# Wash_Hand_v1_3.net
KiCad netlist of a schematic drawn in EAGLE
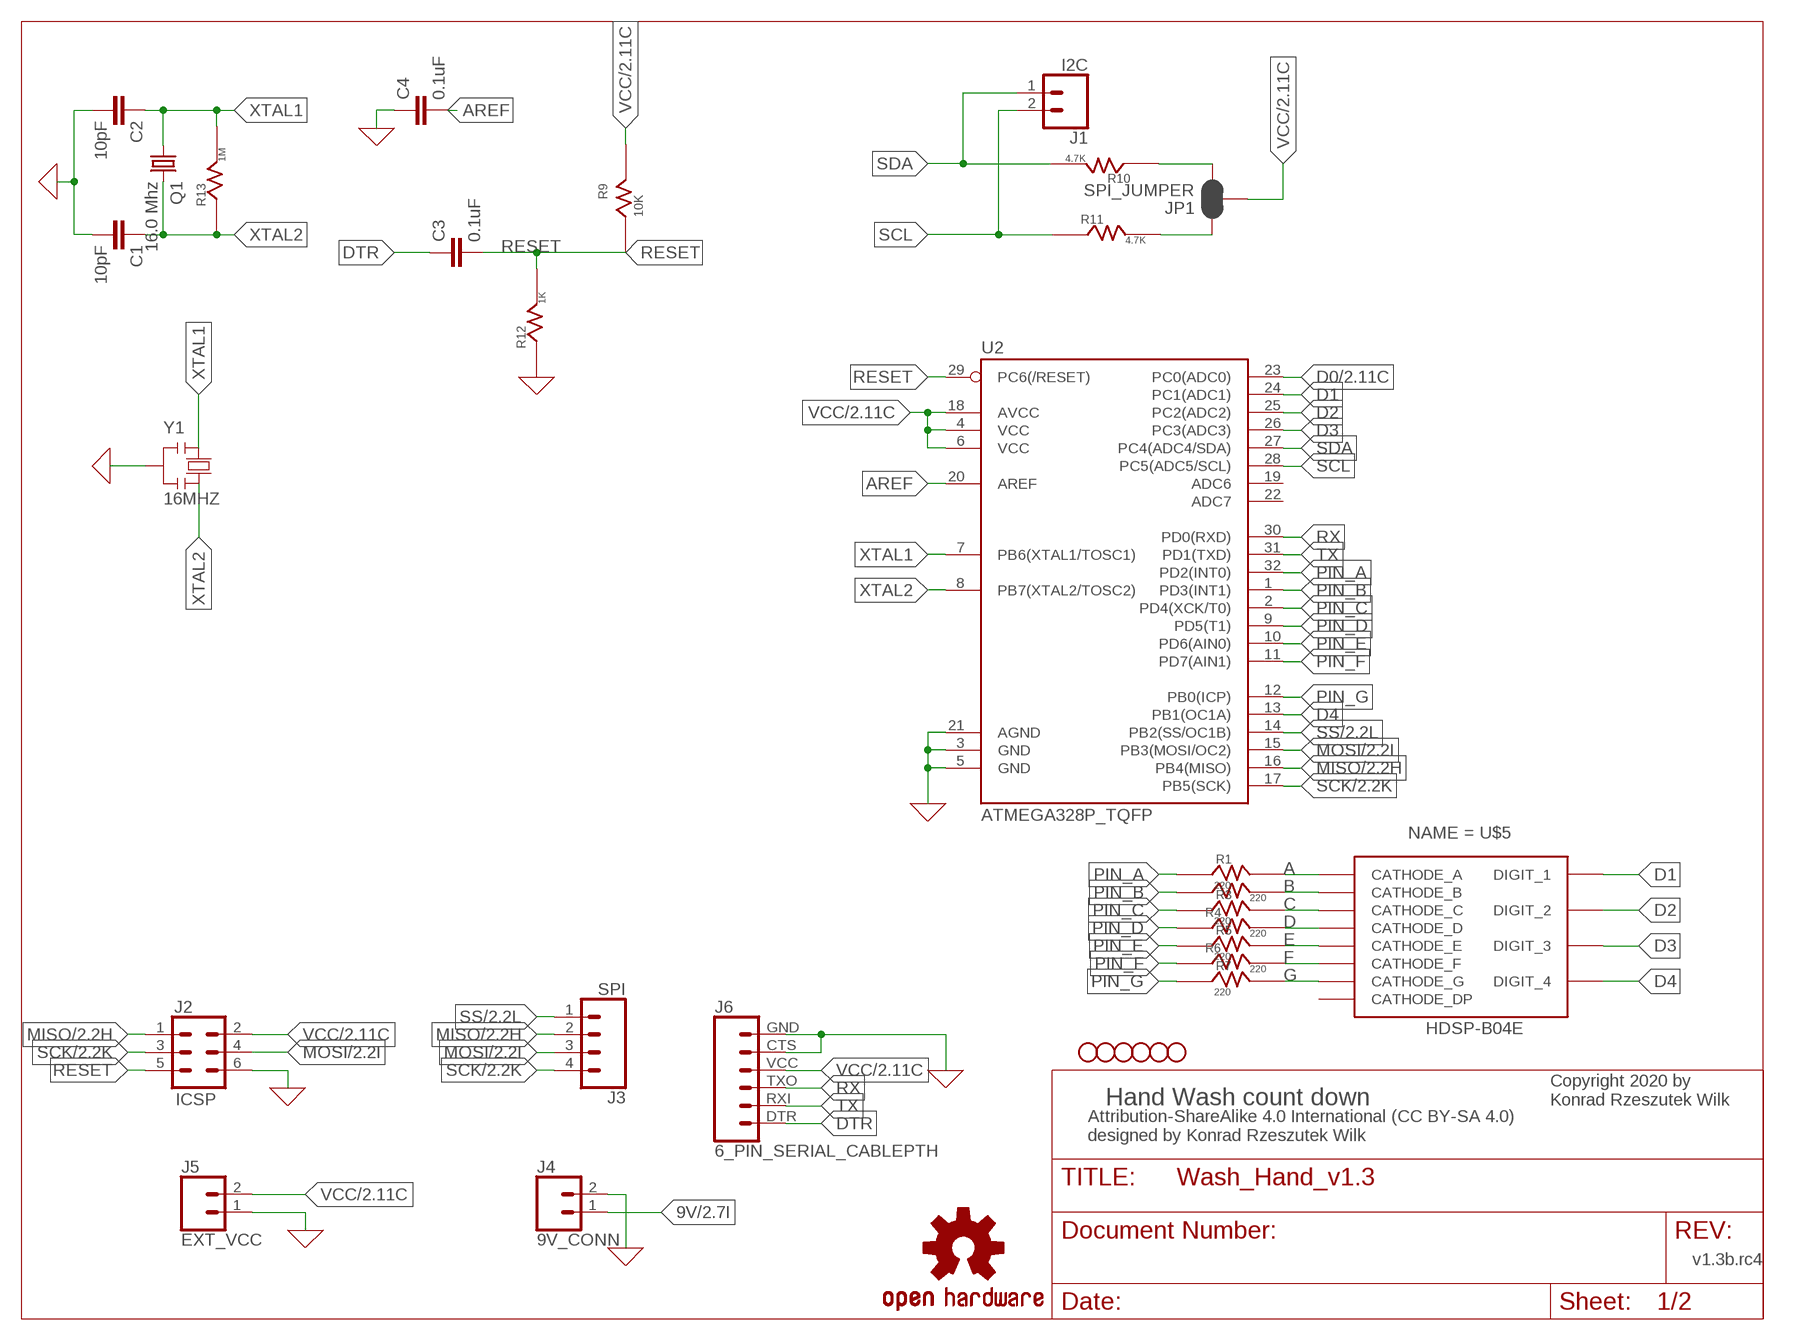
[diagram p0: schematic, sheet 1]
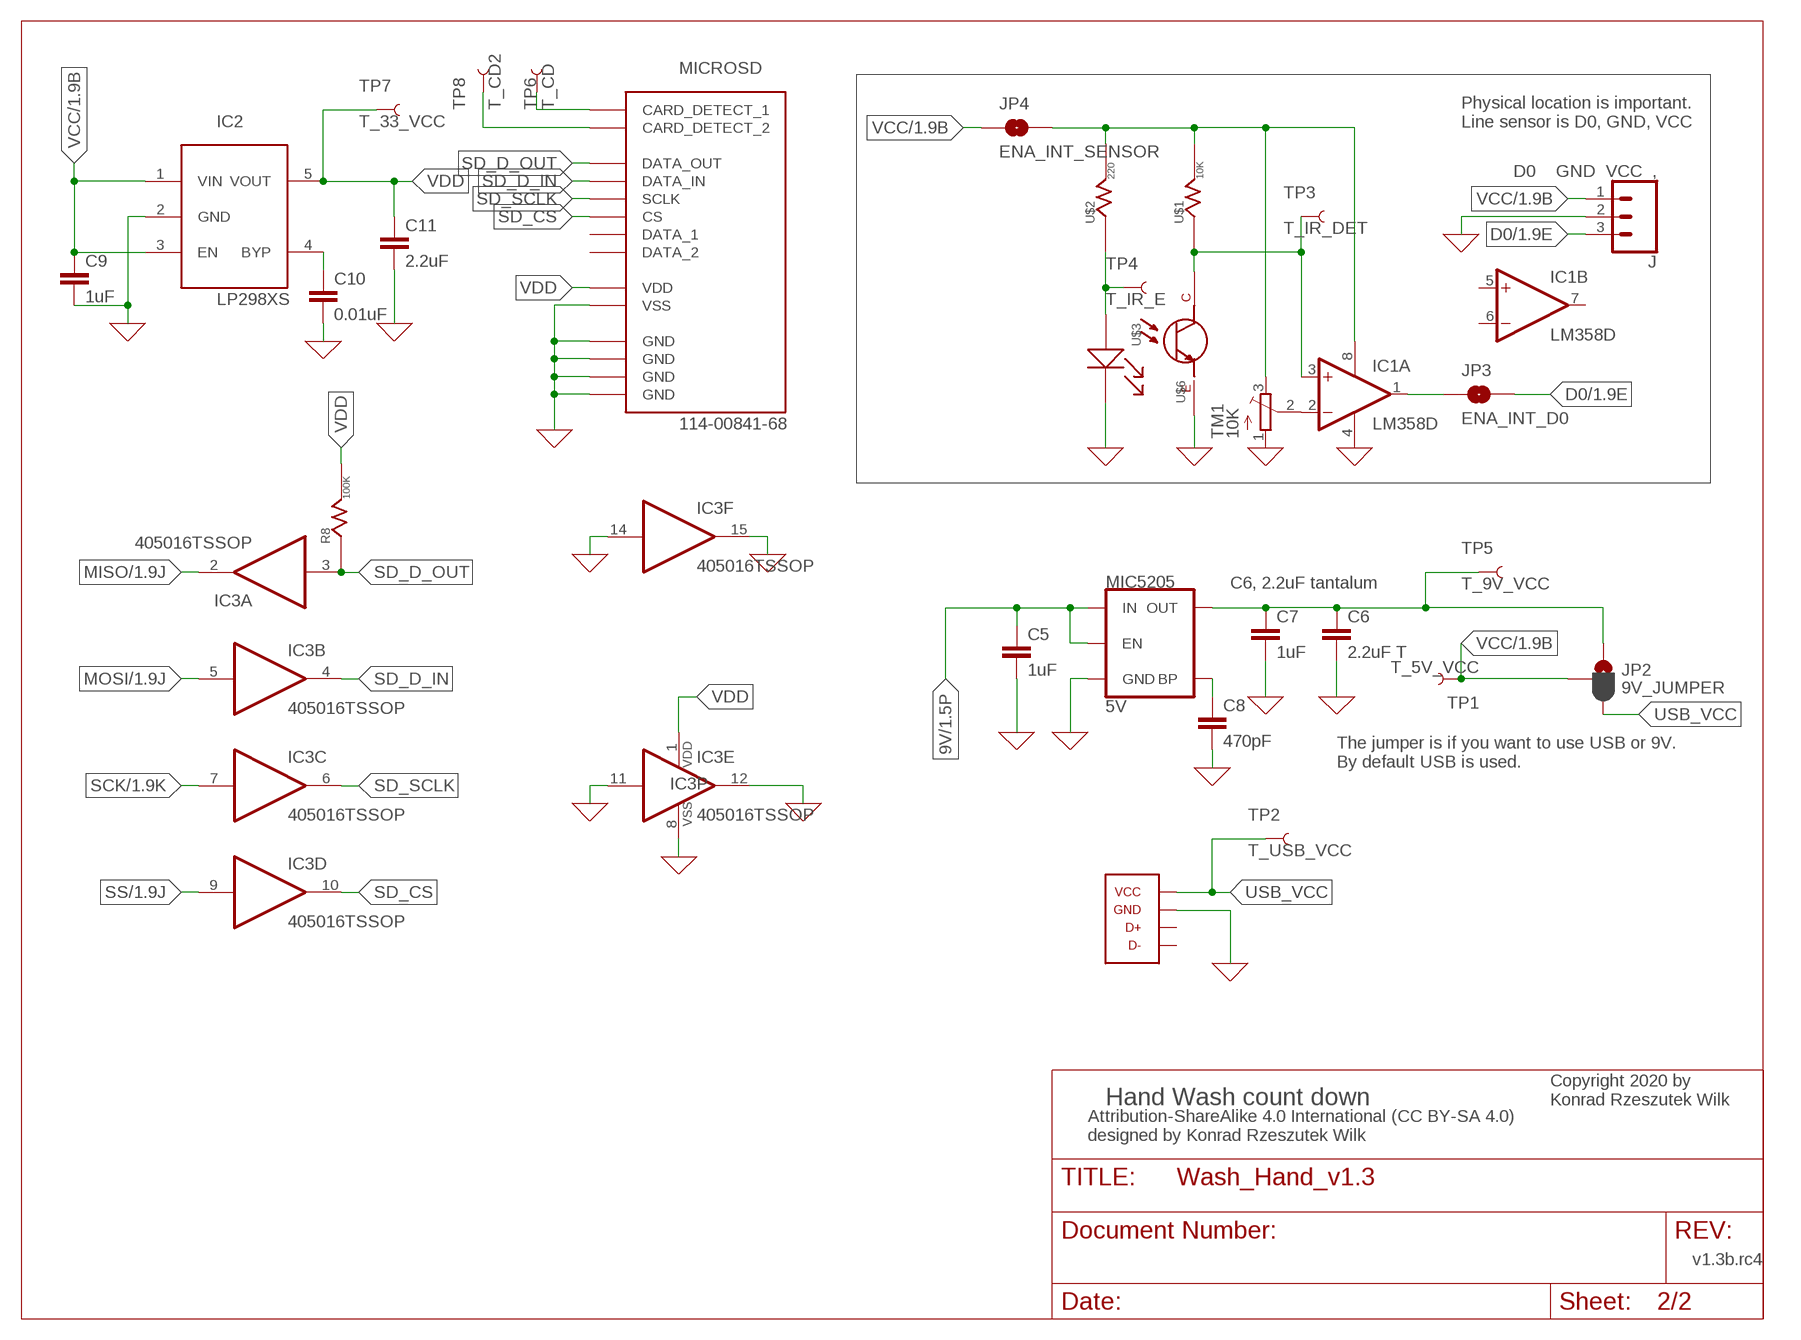
[diagram p1: schematic, sheet 2]

(export (version "E")
  (design (tool "Eeschema 10.0.6"))
  (components
    (comp (ref "C1")
      (value "10pF")
      (footprint "eagle-import:1206")
      (libsource (lib "eagle-import") (part "10UF-1206-6.3V-20%"))
    )
    (comp (ref "C2")
      (value "10pF")
      (footprint "eagle-import:1206")
      (libsource (lib "eagle-import") (part "10UF-1206-6.3V-20%"))
    )
    (comp (ref "C3")
      (value "0.1uF")
      (footprint "eagle-import:1206")
      (libsource (lib "eagle-import") (part "1.0UF-1206-50V-10%"))
    )
    (comp (ref "C4")
      (value "0.1uF")
      (footprint "eagle-import:1206")
      (libsource (lib "eagle-import") (part "1.0UF-1206-50V-10%"))
    )
    (comp (ref "H1")
      (value "STAND-OFF")
      (footprint "eagle-import:STAND-OFF")
      (libsource (lib "eagle-import") (part "STAND-OFF"))
    )
    (comp (ref "H2")
      (value "STAND-OFF")
      (footprint "eagle-import:STAND-OFF")
      (libsource (lib "eagle-import") (part "STAND-OFF"))
    )
    (comp (ref "H3")
      (value "STAND-OFF")
      (footprint "eagle-import:STAND-OFF")
      (libsource (lib "eagle-import") (part "STAND-OFF"))
    )
    (comp (ref "H4")
      (value "STAND-OFF")
      (footprint "eagle-import:STAND-OFF")
      (libsource (lib "eagle-import") (part "STAND-OFF"))
    )
    (comp (ref "H5")
      (value "STAND-OFF")
      (footprint "eagle-import:STAND-OFF")
      (libsource (lib "eagle-import") (part "STAND-OFF"))
    )
    (comp (ref "H6")
      (value "STAND-OFF")
      (footprint "eagle-import:STAND-OFF")
      (libsource (lib "eagle-import") (part "STAND-OFF"))
    )
    (comp (ref "J1")
      (value "I2C")
      (footprint "eagle-import:1X02")
      (libsource (lib "eagle-import") (part "CONN_02"))
    )
    (comp (ref "J2")
      (value "ICSP")
      (footprint "eagle-import:2X3")
      (libsource (lib "eagle-import") (part "CONN_03X2FEMALE"))
    )
    (comp (ref "J3")
      (value "SPI")
      (footprint "eagle-import:1X04")
      (libsource (lib "eagle-import") (part "CONN_04"))
    )
    (comp (ref "J4")
      (value "9V_CONN")
      (footprint "eagle-import:1X02")
      (libsource (lib "eagle-import") (part "CONN_02"))
    )
    (comp (ref "J5")
      (value "EXT_VCC")
      (footprint "eagle-import:1X02")
      (libsource (lib "eagle-import") (part "CONN_02"))
    )
    (comp (ref "J6")
      (value "6_PIN_SERIAL_CABLEPTH")
      (footprint "eagle-import:FTDI_BASIC")
      (libsource (lib "eagle-import") (part "6_PIN_SERIAL_CABLEPTH"))
    )
    (comp (ref "JP1")
      (value "SPI_JUMPER")
      (footprint "eagle-import:SMT-JUMPER_3_2-NC_PASTE_SILK")
      (libsource (lib "eagle-import") (part "JUMPER-SMT_3_2-NC_PASTE_SILK"))
    )
    (comp (ref "LOGO1")
      (value "OSHW-LOGOM")
      (footprint "eagle-import:OSHW-LOGO-M")
      (libsource (lib "eagle-import") (part "OSHW-LOGOM"))
    )
    (comp (ref "Q1")
      (value "16.0 Mhz")
      (footprint "eagle-import:HC49_S")
      (libsource (lib "eagle-import") (part "CRYSTALHC49S"))
    )
    (comp (ref "R1")
      (value "220")
      (footprint "eagle-import:1206")
      (libsource (lib "eagle-import") (part "RESISTORR1206"))
    )
    (comp (ref "R2")
      (value "220")
      (footprint "eagle-import:1206")
      (libsource (lib "eagle-import") (part "RESISTORR1206"))
    )
    (comp (ref "R3")
      (value "220")
      (footprint "eagle-import:1206")
      (libsource (lib "eagle-import") (part "RESISTORR1206"))
    )
    (comp (ref "R4")
      (value "220")
      (footprint "eagle-import:1206")
      (libsource (lib "eagle-import") (part "RESISTORR1206"))
    )
    (comp (ref "R5")
      (value "220")
      (footprint "eagle-import:1206")
      (libsource (lib "eagle-import") (part "RESISTORR1206"))
    )
    (comp (ref "R6")
      (value "220")
      (footprint "eagle-import:1206")
      (libsource (lib "eagle-import") (part "RESISTORR1206"))
    )
    (comp (ref "R7")
      (value "220")
      (footprint "eagle-import:1206")
      (libsource (lib "eagle-import") (part "RESISTORR1206"))
    )
    (comp (ref "R9")
      (value "10K")
      (footprint "eagle-import:1206")
      (libsource (lib "eagle-import") (part "RESISTORR1206"))
    )
    (comp (ref "R10")
      (value "4.7K")
      (footprint "eagle-import:1206")
      (libsource (lib "eagle-import") (part "RESISTORR1206"))
    )
    (comp (ref "R11")
      (value "4.7K")
      (footprint "eagle-import:1206")
      (libsource (lib "eagle-import") (part "RESISTORR1206"))
    )
    (comp (ref "R12")
      (value "1K")
      (footprint "eagle-import:1206")
      (libsource (lib "eagle-import") (part "RESISTORR1206"))
    )
    (comp (ref "R13")
      (value "1M")
      (footprint "eagle-import:1206")
      (libsource (lib "eagle-import") (part "RESISTORR1206"))
    )
    (comp (ref "U$5")
      (value "HDSP-B04E")
      (footprint "eagle-import:HDSP-B0XE")
      (libsource (lib "eagle-import") (part "HDSP-B04E"))
    )
    (comp (ref "U2")
      (value "ATMEGA328P_TQFP")
      (footprint "eagle-import:TQFP32-08")
      (libsource (lib "eagle-import") (part "ATMEGA328P_TQFP"))
    )
    (comp (ref "Y1")
      (value "16MHZ")
      (footprint "eagle-import:RESONATOR")
      (libsource (lib "eagle-import") (part "RESONATORMU"))
    )
    (comp (ref "C5")
      (value "1uF")
      (footprint "eagle-import:1206")
      (libsource (lib "eagle-import") (part "1.0UF-1206-50V-10%"))
    )
    (comp (ref "C6")
      (value "2.2uF T")
      (footprint "eagle-import:1206")
      (libsource (lib "eagle-import") (part "1.0UF-1206-50V-10%"))
    )
    (comp (ref "C7")
      (value "1uF")
      (footprint "eagle-import:1206")
      (libsource (lib "eagle-import") (part "1.0UF-1206-50V-10%"))
    )
    (comp (ref "C8")
      (value "470pF")
      (footprint "eagle-import:1206")
      (libsource (lib "eagle-import") (part "1.0UF-1206-50V-10%"))
    )
    (comp (ref "C9")
      (value "1uF")
      (footprint "eagle-import:1206")
      (libsource (lib "eagle-import") (part "1.0UF-1206-50V-10%"))
    )
    (comp (ref "C10")
      (value "0.01uF")
      (footprint "eagle-import:1206")
      (libsource (lib "eagle-import") (part "1.0UF-1206-50V-10%"))
    )
    (comp (ref "C11")
      (value "2.2uF")
      (footprint "eagle-import:1206")
      (libsource (lib "eagle-import") (part "1.0UF-1206-50V-10%"))
    )
    (comp (ref "IC1")
      (value "LM358D")
      (footprint "eagle-import:SO08")
      (libsource (lib "eagle-import") (part "LM358D"))
    )
    (comp (ref "IC2")
      (value "LP298XS")
      (footprint "eagle-import:SOT23-5L")
      (libsource (lib "eagle-import") (part "LP298XS"))
    )
    (comp (ref "IC3")
      (value "405016TSSOP")
      (footprint "eagle-import:TSSOP16")
      (libsource (lib "eagle-import") (part "405016TSSOP"))
    )
    (comp (ref "J")
      (value "D0 GND VCC ,")
      (footprint "eagle-import:1X03")
      (libsource (lib "eagle-import") (part "CONN_03"))
    )
    (comp (ref "JP2")
      (value "9V_JUMPER")
      (footprint "eagle-import:SMT-JUMPER_3_1-NC_PASTE_SILK")
      (libsource (lib "eagle-import") (part "JUMPER-SMT_3_1-NC_PASTE_SILK"))
    )
    (comp (ref "JP3")
      (value "ENA_INT_D0")
      (footprint "eagle-import:SMT-JUMPER_2_NO_NO-SILK_ROUND")
      (libsource (lib "eagle-import") (part "JUMPER-SMT_2_NO_NO-SILK_ROUND"))
    )
    (comp (ref "JP4")
      (value "ENA_INT_SENSOR")
      (footprint "eagle-import:SMT-JUMPER_2_NO_NO-SILK_ROUND")
      (libsource (lib "eagle-import") (part "JUMPER-SMT_2_NO_NO-SILK_ROUND"))
    )
    (comp (ref "MIC5205")
      (value "5V")
      (footprint "eagle-import:SOT23-5")
      (libsource (lib "eagle-import") (part "V_REG_MIC52055V"))
    )
    (comp (ref "MICROSD")
      (value "114-00841-68")
      (footprint "eagle-import:114-00841-68")
      (libsource (lib "eagle-import") (part "114-00841-68"))
    )
    (comp (ref "R8")
      (value "100K")
      (footprint "eagle-import:1206")
      (libsource (lib "eagle-import") (part "RESISTORR1206"))
    )
    (comp (ref "TM1")
      (value "10K")
      (footprint "eagle-import:TC33X")
      (libsource (lib "eagle-import") (part "TRIMPOTTC33X"))
    )
    (comp (ref "TP1")
      (value "T_5V_VCC")
      (footprint "eagle-import:PAD.03X.04")
      (libsource (lib "eagle-import") (part "TEST-POINT3X4"))
    )
    (comp (ref "TP2")
      (value "T_USB_VCC")
      (footprint "eagle-import:PAD.03X.04")
      (libsource (lib "eagle-import") (part "TEST-POINT3X4"))
    )
    (comp (ref "TP3")
      (value "T_IR_DET")
      (footprint "eagle-import:PAD.03X.04")
      (libsource (lib "eagle-import") (part "TEST-POINT3X4"))
    )
    (comp (ref "TP4")
      (value "T_IR_E")
      (footprint "eagle-import:PAD.03X.04")
      (libsource (lib "eagle-import") (part "TEST-POINT3X4"))
    )
    (comp (ref "TP5")
      (value "T_9V_VCC")
      (footprint "eagle-import:PAD.03X.04")
      (libsource (lib "eagle-import") (part "TEST-POINT3X4"))
    )
    (comp (ref "TP6")
      (value "T_CD")
      (footprint "eagle-import:PAD.03X.04")
      (libsource (lib "eagle-import") (part "TEST-POINT3X4"))
    )
    (comp (ref "TP7")
      (value "T_33_VCC")
      (footprint "eagle-import:PAD.03X.04")
      (libsource (lib "eagle-import") (part "TEST-POINT3X4"))
    )
    (comp (ref "TP8")
      (value "T_CD2")
      (footprint "eagle-import:PAD.03X.04")
      (libsource (lib "eagle-import") (part "TEST-POINT3X4"))
    )
    (comp (ref "U$1")
      (value "10K")
      (footprint "eagle-import:1206")
      (libsource (lib "eagle-import") (part "RESISTORR1206"))
    )
    (comp (ref "U$2")
      (value "220")
      (footprint "eagle-import:1206")
      (libsource (lib "eagle-import") (part "RESISTORR1206"))
    )
    (comp (ref "U$3")
      (value "LTE-302")
      (footprint "eagle-import:LTE-302")
      (libsource (lib "eagle-import") (part "LTE-302"))
    )
    (comp (ref "U$4")
      (value "USB_MICROB_10118194_AMPHENOL")
      (footprint "eagle-import:USB_MICROB_10118194_AMPHENOL")
      (libsource (lib "eagle-import") (part "USB_MICROB_10118194_AMPHENOL"))
    )
    (comp (ref "U$6")
      (value "LTR-301")
      (footprint "eagle-import:LTR-301")
      (libsource (lib "eagle-import") (part "LTR-301"))
    )
  )
  (nets
    (net (code "1") (name "0") (class "Default")
      (node (ref "C1") (pin "2") (pinfunction "2_2") (pintype "passive"))
      (node (ref "C10") (pin "2") (pinfunction "2_2") (pintype "passive"))
      (node (ref "C11") (pin "2") (pinfunction "2_2") (pintype "passive"))
      (node (ref "C2") (pin "2") (pinfunction "2_2") (pintype "passive"))
      (node (ref "C4") (pin "1") (pinfunction "1_1") (pintype "passive"))
      (node (ref "C5") (pin "2") (pinfunction "2_2") (pintype "passive"))
      (node (ref "C6") (pin "2") (pinfunction "2_2") (pintype "passive"))
      (node (ref "C7") (pin "2") (pinfunction "2_2") (pintype "passive"))
      (node (ref "C8") (pin "2") (pinfunction "2_2") (pintype "passive"))
      (node (ref "C9") (pin "2") (pinfunction "2_2") (pintype "passive"))
      (node (ref "IC1") (pin "4") (pinfunction "V-_4") (pintype "power_in"))
      (node (ref "IC2") (pin "2") (pinfunction "GND_2") (pintype "bidirectional"))
      (node (ref "IC3") (pin "11") (pinfunction "I_11") (pintype "input"))
      (node (ref "IC3") (pin "12") (pinfunction "O_12") (pintype "output"))
      (node (ref "IC3") (pin "14") (pinfunction "I_14") (pintype "input"))
      (node (ref "IC3") (pin "15") (pinfunction "O_15") (pintype "output"))
      (node (ref "IC3") (pin "8") (pinfunction "VSS_8") (pintype "power_in"))
      (node (ref "J") (pin "2") (pinfunction "2_2") (pintype "passive"))
      (node (ref "J2") (pin "6") (pinfunction "6_6") (pintype "bidirectional"))
      (node (ref "J4") (pin "2") (pinfunction "2_2") (pintype "passive"))
      (node (ref "J5") (pin "1") (pinfunction "1_1") (pintype "passive"))
      (node (ref "J6") (pin "CTS") (pinfunction "5_CTS") (pintype "passive"))
      (node (ref "J6") (pin "GND") (pinfunction "6_GND") (pintype "passive"))
      (node (ref "MIC5205") (pin "2") (pinfunction "GND_2") (pintype "input"))
      (node (ref "MICROSD") (pin "GND$1") (pinfunction "GND_GND$1") (pintype "power_in"))
      (node (ref "MICROSD") (pin "GND$2") (pinfunction "GND_GND$2") (pintype "power_in"))
      (node (ref "MICROSD") (pin "GND$3") (pinfunction "GND_GND$3") (pintype "power_in"))
      (node (ref "MICROSD") (pin "GND$4") (pinfunction "GND_GND$4") (pintype "power_in"))
      (node (ref "MICROSD") (pin "VSS") (pinfunction "VSS_VSS") (pintype "power_in"))
      (node (ref "R12") (pin "1") (pinfunction "R_1_1") (pintype "bidirectional"))
      (node (ref "TM1") (pin "1") (pinfunction "A_1") (pintype "passive"))
      (node (ref "U$3") (pin "C") (pinfunction "K$1_C") (pintype "tri_state"))
      (node (ref "U$4") (pin "5") (pinfunction "GND_5") (pintype "bidirectional"))
      (node (ref "U$6") (pin "E") (pinfunction "E$1_E") (pintype "input"))
      (node (ref "U2") (pin "21") (pinfunction "AGND_21") (pintype "bidirectional"))
      (node (ref "U2") (pin "3") (pinfunction "GND_3") (pintype "bidirectional"))
      (node (ref "U2") (pin "5") (pinfunction "GND_5") (pintype "bidirectional"))
      (node (ref "Y1") (pin "2") (pinfunction "2_2") (pintype "passive"))
    )
    (net (code "2") (name "9V") (class "Default")
      (node (ref "C5") (pin "1") (pinfunction "1_1") (pintype "passive"))
      (node (ref "J4") (pin "1") (pinfunction "1_1") (pintype "passive"))
      (node (ref "MIC5205") (pin "1") (pinfunction "IN_1") (pintype "input"))
      (node (ref "MIC5205") (pin "3") (pinfunction "EN_3") (pintype "input"))
    )
    (net (code "3") (name "A") (class "Default")
      (node (ref "R1") (pin "2") (pinfunction "R_2_2") (pintype "bidirectional"))
      (node (ref "U$5") (pin "PIN$11") (pinfunction "CATHODE_A_PIN$11") (pintype "input"))
    )
    (net (code "4") (name "AREF") (class "Default")
      (node (ref "C4") (pin "2") (pinfunction "2_2") (pintype "passive"))
      (node (ref "U2") (pin "20") (pinfunction "AREF_20") (pintype "bidirectional"))
    )
    (net (code "5") (name "B") (class "Default")
      (node (ref "R2") (pin "2") (pinfunction "R_2_2") (pintype "bidirectional"))
      (node (ref "U$5") (pin "PIN$7") (pinfunction "CATHODE_B_PIN$7") (pintype "input"))
    )
    (net (code "6") (name "C") (class "Default")
      (node (ref "R3") (pin "2") (pinfunction "R_2_2") (pintype "bidirectional"))
      (node (ref "U$5") (pin "PIN$4") (pinfunction "CATHODE_C_PIN$4") (pintype "input"))
    )
    (net (code "7") (name "D") (class "Default")
      (node (ref "R4") (pin "2") (pinfunction "R_2_2") (pintype "bidirectional"))
      (node (ref "U$5") (pin "PIN$2") (pinfunction "CATHODE_D_PIN$2") (pintype "input"))
    )
    (net (code "8") (name "D0") (class "Default")
      (node (ref "IC1") (pin "1") (pinfunction "OUT_1") (pintype "output"))
      (node (ref "J") (pin "3") (pinfunction "3_3") (pintype "passive"))
      (node (ref "JP3") (pin "1") (pinfunction "1_1") (pintype "passive"))
      (node (ref "JP3") (pin "2") (pinfunction "2_2") (pintype "passive"))
      (node (ref "U2") (pin "23") (pinfunction "PC0(ADC0)_23") (pintype "bidirectional"))
    )
    (net (code "9") (name "D1") (class "Default")
      (node (ref "U$5") (pin "PIN12") (pinfunction "DIGIT_1_PIN12") (pintype "input"))
      (node (ref "U2") (pin "24") (pinfunction "PC1(ADC1)_24") (pintype "bidirectional"))
    )
    (net (code "10") (name "D2") (class "Default")
      (node (ref "U$5") (pin "PIN$9") (pinfunction "DIGIT_2_PIN$9") (pintype "input"))
      (node (ref "U2") (pin "25") (pinfunction "PC2(ADC2)_25") (pintype "bidirectional"))
    )
    (net (code "11") (name "D3") (class "Default")
      (node (ref "U$5") (pin "PIN$8") (pinfunction "DIGIT_3_PIN$8") (pintype "input"))
      (node (ref "U2") (pin "26") (pinfunction "PC3(ADC3)_26") (pintype "bidirectional"))
    )
    (net (code "12") (name "D4") (class "Default")
      (node (ref "U$5") (pin "PIN$6") (pinfunction "DIGIT_4_PIN$6") (pintype "input"))
      (node (ref "U2") (pin "13") (pinfunction "PB1(OC1A)_13") (pintype "bidirectional"))
    )
    (net (code "13") (name "DTR") (class "Default")
      (node (ref "C3") (pin "1") (pinfunction "1_1") (pintype "passive"))
      (node (ref "J6") (pin "DTR") (pinfunction "1_DTR") (pintype "passive"))
    )
    (net (code "14") (name "E") (class "Default")
      (node (ref "R5") (pin "2") (pinfunction "R_2_2") (pintype "bidirectional"))
      (node (ref "U$5") (pin "PIN$1") (pinfunction "CATHODE_E_PIN$1") (pintype "input"))
    )
    (net (code "15") (name "F") (class "Default")
      (node (ref "R6") (pin "2") (pinfunction "R_2_2") (pintype "bidirectional"))
      (node (ref "U$5") (pin "PIN$10") (pinfunction "CATHODE_F_PIN$10") (pintype "input"))
    )
    (net (code "16") (name "G") (class "Default")
      (node (ref "R7") (pin "2") (pinfunction "R_2_2") (pintype "bidirectional"))
      (node (ref "U$5") (pin "PIN$5") (pinfunction "CATHODE_G_PIN$5") (pintype "input"))
    )
    (net (code "17") (name "MISO") (class "Default")
      (node (ref "IC3") (pin "2") (pinfunction "O_2") (pintype "output"))
      (node (ref "J2") (pin "1") (pinfunction "1_1") (pintype "bidirectional"))
      (node (ref "J3") (pin "2") (pinfunction "2_2") (pintype "passive"))
      (node (ref "U2") (pin "16") (pinfunction "PB4(MISO)_16") (pintype "bidirectional"))
    )
    (net (code "18") (name "MOSI") (class "Default")
      (node (ref "IC3") (pin "5") (pinfunction "I_5") (pintype "input"))
      (node (ref "J2") (pin "4") (pinfunction "4_4") (pintype "bidirectional"))
      (node (ref "J3") (pin "3") (pinfunction "3_3") (pintype "passive"))
      (node (ref "U2") (pin "15") (pinfunction "PB3(MOSI/OC2)_15") (pintype "bidirectional"))
    )
    (net (code "19") (name "Net-(IC1A-+IN)") (class "Default")
      (node (ref "IC1") (pin "3") (pinfunction "+IN_3") (pintype "input"))
      (node (ref "TP3") (pin "P$1") (pinfunction "1_P$1") (pintype "bidirectional"))
      (node (ref "U$1") (pin "1") (pinfunction "R_1_1") (pintype "bidirectional"))
      (node (ref "U$6") (pin "C") (pinfunction "C$1_C") (pintype "tri_state"))
    )
    (net (code "20") (name "Net-(IC1A--IN)") (class "Default")
      (node (ref "IC1") (pin "2") (pinfunction "-IN_2") (pintype "input"))
      (node (ref "TM1") (pin "2") (pinfunction "S_2") (pintype "passive"))
    )
    (net (code "21") (name "Net-(IC1C-V+)") (class "Default")
      (node (ref "IC1") (pin "8") (pinfunction "V+_8") (pintype "power_in"))
      (node (ref "JP4") (pin "2") (pinfunction "2_2") (pintype "passive"))
      (node (ref "TM1") (pin "3") (pinfunction "E_3") (pintype "passive"))
      (node (ref "U$1") (pin "2") (pinfunction "R_2_2") (pintype "bidirectional"))
      (node (ref "U$2") (pin "2") (pinfunction "R_2_2") (pintype "bidirectional"))
    )
    (net (code "22") (name "Net-(IC2-BYP)") (class "Default")
      (node (ref "C10") (pin "1") (pinfunction "1_1") (pintype "passive"))
      (node (ref "IC2") (pin "4") (pinfunction "BYP_4") (pintype "bidirectional"))
    )
    (net (code "23") (name "Net-(MIC5205-BP)") (class "Default")
      (node (ref "C8") (pin "1") (pinfunction "1_1") (pintype "passive"))
      (node (ref "MIC5205") (pin "4") (pinfunction "BP_4") (pintype "input"))
    )
    (net (code "24") (name "Net-(MIC5205-OUT)") (class "Default")
      (node (ref "C6") (pin "1") (pinfunction "1_1") (pintype "passive"))
      (node (ref "C7") (pin "1") (pinfunction "1_1") (pintype "passive"))
      (node (ref "JP2") (pin "1") (pinfunction "1_1") (pintype "passive"))
      (node (ref "MIC5205") (pin "5") (pinfunction "OUT_5") (pintype "passive"))
      (node (ref "TP5") (pin "P$1") (pinfunction "1_P$1") (pintype "bidirectional"))
    )
    (net (code "25") (name "Net-(MICROSD-CARD_DETECT_1)") (class "Default")
      (node (ref "MICROSD") (pin "CD_SW_1") (pinfunction "CARD_DETECT_1_CD_SW_1") (pintype "output"))
      (node (ref "TP6") (pin "P$1") (pinfunction "1_P$1") (pintype "bidirectional"))
    )
    (net (code "26") (name "Net-(MICROSD-CARD_DETECT_2)") (class "Default")
      (node (ref "MICROSD") (pin "CD_SW_2") (pinfunction "CARD_DETECT_2_CD_SW_2") (pintype "bidirectional"))
      (node (ref "TP8") (pin "P$1") (pinfunction "1_P$1") (pintype "bidirectional"))
    )
    (net (code "27") (name "Net-(R10-R_1)") (class "Default")
      (node (ref "JP1") (pin "3") (pinfunction "3_3") (pintype "passive"))
      (node (ref "R10") (pin "1") (pinfunction "R_1_1") (pintype "bidirectional"))
    )
    (net (code "28") (name "Net-(R11-R_2)") (class "Default")
      (node (ref "JP1") (pin "1") (pinfunction "1_1") (pintype "passive"))
      (node (ref "R11") (pin "2") (pinfunction "R_2_2") (pintype "bidirectional"))
    )
    (net (code "29") (name "Net-(TP4-1)") (class "Default")
      (node (ref "TP4") (pin "P$1") (pinfunction "1_P$1") (pintype "bidirectional"))
      (node (ref "U$2") (pin "1") (pinfunction "R_1_1") (pintype "bidirectional"))
      (node (ref "U$3") (pin "A") (pinfunction "A$1_A") (pintype "bidirectional"))
    )
    (net (code "30") (name "PIN_A") (class "Default")
      (node (ref "R1") (pin "1") (pinfunction "R_1_1") (pintype "bidirectional"))
      (node (ref "U2") (pin "32") (pinfunction "PD2(INT0)_32") (pintype "bidirectional"))
    )
    (net (code "31") (name "PIN_B") (class "Default")
      (node (ref "R2") (pin "1") (pinfunction "R_1_1") (pintype "bidirectional"))
      (node (ref "U2") (pin "1") (pinfunction "PD3(INT1)_1") (pintype "bidirectional"))
    )
    (net (code "32") (name "PIN_C") (class "Default")
      (node (ref "R3") (pin "1") (pinfunction "R_1_1") (pintype "bidirectional"))
      (node (ref "U2") (pin "2") (pinfunction "PD4(XCK/T0)_2") (pintype "bidirectional"))
    )
    (net (code "33") (name "PIN_D") (class "Default")
      (node (ref "R4") (pin "1") (pinfunction "R_1_1") (pintype "bidirectional"))
      (node (ref "U2") (pin "9") (pinfunction "PD5(T1)_9") (pintype "bidirectional"))
    )
    (net (code "34") (name "PIN_E") (class "Default")
      (node (ref "R5") (pin "1") (pinfunction "R_1_1") (pintype "bidirectional"))
      (node (ref "U2") (pin "10") (pinfunction "PD6(AIN0)_10") (pintype "bidirectional"))
    )
    (net (code "35") (name "PIN_F") (class "Default")
      (node (ref "R6") (pin "1") (pinfunction "R_1_1") (pintype "bidirectional"))
      (node (ref "U2") (pin "11") (pinfunction "PD7(AIN1)_11") (pintype "bidirectional"))
    )
    (net (code "36") (name "PIN_G") (class "Default")
      (node (ref "R7") (pin "1") (pinfunction "R_1_1") (pintype "bidirectional"))
      (node (ref "U2") (pin "12") (pinfunction "PB0(ICP)_12") (pintype "bidirectional"))
    )
    (net (code "37") (name "RESET") (class "Default")
      (node (ref "C3") (pin "2") (pinfunction "2_2") (pintype "passive"))
      (node (ref "J2") (pin "5") (pinfunction "5_5") (pintype "bidirectional"))
      (node (ref "R12") (pin "2") (pinfunction "R_2_2") (pintype "bidirectional"))
      (node (ref "R9") (pin "1") (pinfunction "R_1_1") (pintype "bidirectional"))
      (node (ref "U2") (pin "29") (pinfunction "PC6(/RESET)_29") (pintype "bidirectional"))
    )
    (net (code "38") (name "RX") (class "Default")
      (node (ref "J6") (pin "TXO") (pinfunction "3_TXO") (pintype "passive"))
      (node (ref "U2") (pin "30") (pinfunction "PD0(RXD)_30") (pintype "bidirectional"))
    )
    (net (code "39") (name "SCK") (class "Default")
      (node (ref "IC3") (pin "7") (pinfunction "I_7") (pintype "input"))
      (node (ref "J2") (pin "3") (pinfunction "3_3") (pintype "bidirectional"))
      (node (ref "J3") (pin "4") (pinfunction "4_4") (pintype "passive"))
      (node (ref "U2") (pin "17") (pinfunction "PB5(SCK)_17") (pintype "bidirectional"))
    )
    (net (code "40") (name "SCL") (class "Default")
      (node (ref "J1") (pin "2") (pinfunction "2_2") (pintype "passive"))
      (node (ref "R11") (pin "1") (pinfunction "R_1_1") (pintype "bidirectional"))
      (node (ref "U2") (pin "28") (pinfunction "PC5(ADC5/SCL)_28") (pintype "bidirectional"))
    )
    (net (code "41") (name "SDA") (class "Default")
      (node (ref "J1") (pin "1") (pinfunction "1_1") (pintype "passive"))
      (node (ref "R10") (pin "2") (pinfunction "R_2_2") (pintype "bidirectional"))
      (node (ref "U2") (pin "27") (pinfunction "PC4(ADC4/SDA)_27") (pintype "bidirectional"))
    )
    (net (code "42") (name "SD_CS") (class "Default")
      (node (ref "IC3") (pin "10") (pinfunction "O_10") (pintype "output"))
      (node (ref "MICROSD") (pin "CS") (pinfunction "CS_CS") (pintype "bidirectional"))
    )
    (net (code "43") (name "SD_D_IN") (class "Default")
      (node (ref "IC3") (pin "4") (pinfunction "O_4") (pintype "output"))
      (node (ref "MICROSD") (pin "DATA_IN") (pinfunction "DATA_IN_DATA_IN") (pintype "bidirectional"))
    )
    (net (code "44") (name "SD_D_OUT") (class "Default")
      (node (ref "IC3") (pin "3") (pinfunction "I_3") (pintype "input"))
      (node (ref "MICROSD") (pin "DATA_OUT") (pinfunction "DATA_OUT_DATA_OUT") (pintype "bidirectional"))
      (node (ref "R8") (pin "1") (pinfunction "R_1_1") (pintype "bidirectional"))
    )
    (net (code "45") (name "SD_SCLK") (class "Default")
      (node (ref "IC3") (pin "6") (pinfunction "O_6") (pintype "output"))
      (node (ref "MICROSD") (pin "SCLK") (pinfunction "SCLK_SCLK") (pintype "bidirectional"))
    )
    (net (code "46") (name "SS") (class "Default")
      (node (ref "IC3") (pin "9") (pinfunction "I_9") (pintype "input"))
      (node (ref "J3") (pin "1") (pinfunction "1_1") (pintype "passive"))
      (node (ref "U2") (pin "14") (pinfunction "PB2(SS/OC1B)_14") (pintype "bidirectional"))
    )
    (net (code "47") (name "TX") (class "Default")
      (node (ref "J6") (pin "RXI") (pinfunction "2_RXI") (pintype "passive"))
      (node (ref "U2") (pin "31") (pinfunction "PD1(TXD)_31") (pintype "bidirectional"))
    )
    (net (code "48") (name "USB_VCC") (class "Default")
      (node (ref "JP2") (pin "3") (pinfunction "3_3") (pintype "passive"))
      (node (ref "TP2") (pin "P$1") (pinfunction "1_P$1") (pintype "bidirectional"))
      (node (ref "U$4") (pin "1") (pinfunction "VCC_1") (pintype "bidirectional"))
    )
    (net (code "49") (name "VCC") (class "Default")
      (node (ref "C9") (pin "1") (pinfunction "1_1") (pintype "passive"))
      (node (ref "IC2") (pin "1") (pinfunction "VIN_1") (pintype "bidirectional"))
      (node (ref "IC2") (pin "3") (pinfunction "EN_3") (pintype "bidirectional"))
      (node (ref "J") (pin "1") (pinfunction "1_1") (pintype "passive"))
      (node (ref "J2") (pin "2") (pinfunction "2_2") (pintype "bidirectional"))
      (node (ref "J5") (pin "2") (pinfunction "2_2") (pintype "passive"))
      (node (ref "J6") (pin "VCC") (pinfunction "4_VCC") (pintype "passive"))
      (node (ref "JP1") (pin "2") (pinfunction "2_2") (pintype "passive"))
      (node (ref "JP2") (pin "2") (pinfunction "2_2") (pintype "passive"))
      (node (ref "JP4") (pin "1") (pinfunction "1_1") (pintype "passive"))
      (node (ref "R9") (pin "2") (pinfunction "R_2_2") (pintype "bidirectional"))
      (node (ref "TP1") (pin "P$1") (pinfunction "1_P$1") (pintype "bidirectional"))
      (node (ref "U2") (pin "18") (pinfunction "AVCC_18") (pintype "bidirectional"))
      (node (ref "U2") (pin "4") (pinfunction "VCC_4") (pintype "bidirectional"))
      (node (ref "U2") (pin "6") (pinfunction "VCC_6") (pintype "bidirectional"))
    )
    (net (code "50") (name "VDD") (class "Default")
      (node (ref "C11") (pin "1") (pinfunction "1_1") (pintype "passive"))
      (node (ref "IC2") (pin "5") (pinfunction "VOUT_5") (pintype "bidirectional"))
      (node (ref "IC3") (pin "1") (pinfunction "VDD_1") (pintype "power_in"))
      (node (ref "MICROSD") (pin "VDD") (pinfunction "VDD_VDD") (pintype "power_in"))
      (node (ref "R8") (pin "2") (pinfunction "R_2_2") (pintype "bidirectional"))
      (node (ref "TP7") (pin "P$1") (pinfunction "1_P$1") (pintype "bidirectional"))
    )
    (net (code "51") (name "XTAL1") (class "Default")
      (node (ref "C2") (pin "1") (pinfunction "1_1") (pintype "passive"))
      (node (ref "Q1") (pin "1") (pinfunction "1_1") (pintype "passive"))
      (node (ref "R13") (pin "2") (pinfunction "R_2_2") (pintype "bidirectional"))
      (node (ref "U2") (pin "7") (pinfunction "PB6(XTAL1/TOSC1)_7") (pintype "bidirectional"))
      (node (ref "Y1") (pin "1") (pinfunction "1_1") (pintype "passive"))
    )
    (net (code "52") (name "XTAL2") (class "Default")
      (node (ref "C1") (pin "1") (pinfunction "1_1") (pintype "passive"))
      (node (ref "Q1") (pin "2") (pinfunction "2_2") (pintype "passive"))
      (node (ref "R13") (pin "1") (pinfunction "R_1_1") (pintype "bidirectional"))
      (node (ref "U2") (pin "8") (pinfunction "PB7(XTAL2/TOSC2)_8") (pintype "bidirectional"))
      (node (ref "Y1") (pin "3") (pinfunction "3_3") (pintype "passive"))
    )
    (net (code "53") (name "unconnected-(IC1B-+IN-Pad5)") (class "Default")
      (node (ref "IC1") (pin "5") (pinfunction "+IN_5") (pintype "input"))
    )
    (net (code "54") (name "unconnected-(IC1B--IN-Pad6)") (class "Default")
      (node (ref "IC1") (pin "6") (pinfunction "-IN_6") (pintype "input"))
    )
    (net (code "55") (name "unconnected-(IC1B-OUT-Pad7)") (class "Default")
      (node (ref "IC1") (pin "7") (pinfunction "OUT_7") (pintype "output"))
    )
    (net (code "56") (name "unconnected-(MICROSD-PadDATA_1)") (class "Default")
      (node (ref "MICROSD") (pin "DATA_1") (pinfunction "DATA_1_DATA_1") (pintype "bidirectional"))
    )
    (net (code "57") (name "unconnected-(MICROSD-PadDATA_2)") (class "Default")
      (node (ref "MICROSD") (pin "DATA_2") (pinfunction "DATA_2_DATA_2") (pintype "bidirectional"))
    )
    (net (code "58") (name "unconnected-(U$4-D+-Pad3)") (class "Default")
      (node (ref "U$4") (pin "3") (pinfunction "D+_3") (pintype "bidirectional"))
    )
    (net (code "59") (name "unconnected-(U$4-D--Pad2)") (class "Default")
      (node (ref "U$4") (pin "2") (pinfunction "D-_2") (pintype "bidirectional"))
    )
    (net (code "60") (name "unconnected-(U$5-CATHODE_DP-PadPIN$3)") (class "Default")
      (node (ref "U$5") (pin "PIN$3") (pinfunction "CATHODE_DP_PIN$3") (pintype "input"))
    )
    (net (code "61") (name "unconnected-(U2-ADC6-Pad19)") (class "Default")
      (node (ref "U2") (pin "19") (pinfunction "ADC6_19") (pintype "bidirectional"))
    )
    (net (code "62") (name "unconnected-(U2-ADC7-Pad22)") (class "Default")
      (node (ref "U2") (pin "22") (pinfunction "ADC7_22") (pintype "bidirectional"))
    )
  )
)
